# cc2652r_rev_e.net
KiCad netlist of a schematic drawn in EAGLE
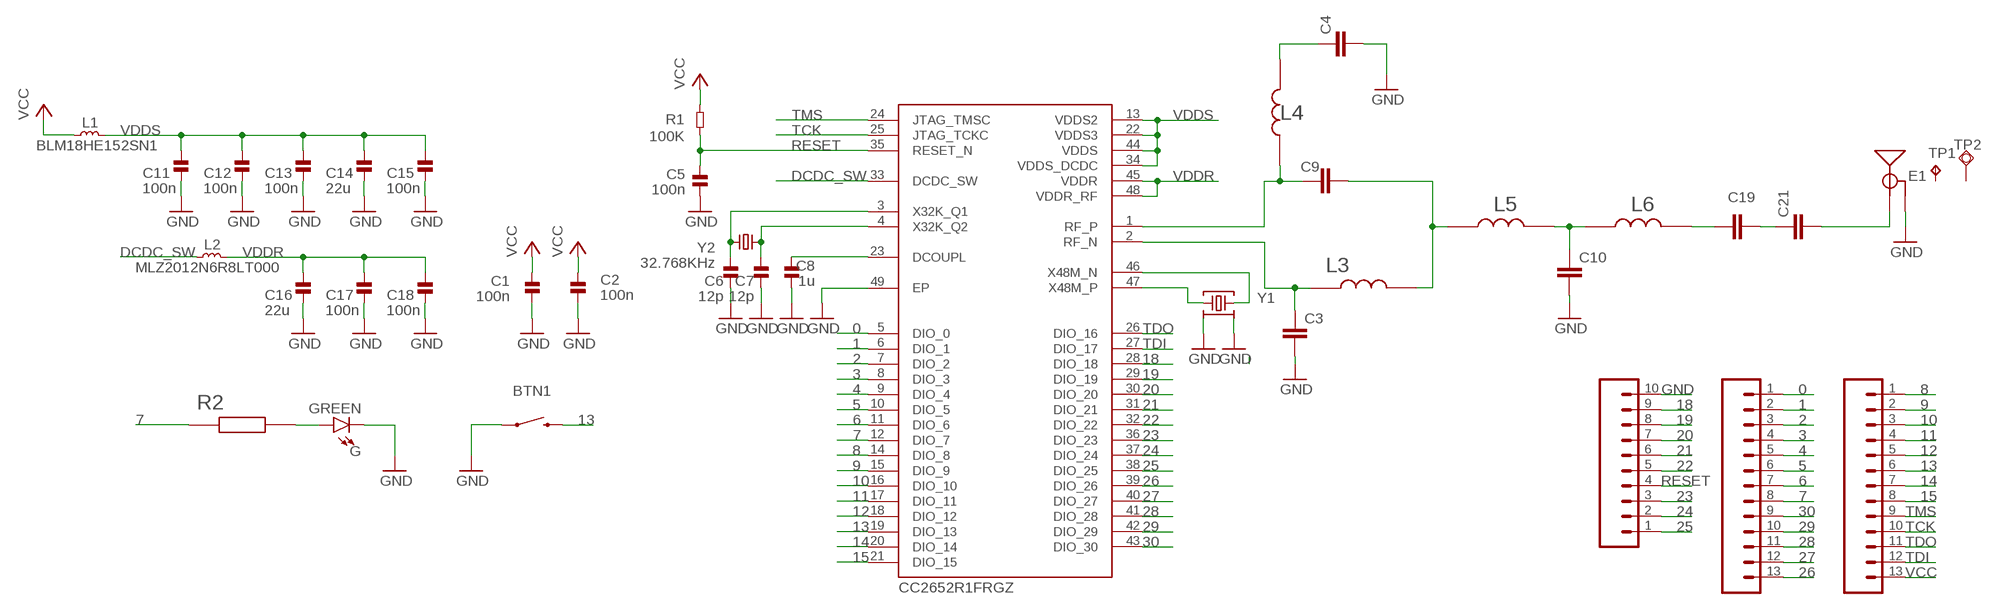
[diagram p0: schematic, sheet 1]

(export (version "E")
  (design (tool "Eeschema 10.0.6"))
  (components
    (comp (ref "BTN1")
      (value "MOMENTARY-SWITCH-SPST-SMD-4.6X2.8MM")
      (footprint "eagle-import:TACTILE_SWITCH_SMD_4.6X2.8MM")
      (libsource (lib "eagle-import") (part "MOMENTARY-SWITCH-SPST-SMD-4.6X2.8MM"))
    )
    (comp (ref "C1")
      (value "100n")
      (footprint "eagle-import:_PKG_C_0402")
      (libsource (lib "eagle-import") (part "CAP-0402"))
    )
    (comp (ref "C2")
      (value "100n")
      (footprint "eagle-import:_PKG_C_0402")
      (libsource (lib "eagle-import") (part "CAP-0402"))
    )
    (comp (ref "C3")
      (value "1pF")
      (footprint "eagle-import:CAPC1005X40N")
      (fields (field (name "MF") "Yageo") (field (name "MP") "RC0402FR-073M6L"))
      (libsource (lib "eagle-import") (part "CAP0402"))
    )
    (comp (ref "C4")
      (value "12pF")
      (footprint "eagle-import:CAPC1005X40N")
      (fields (field (name "MF") "Yageo") (field (name "MP") "RC0402FR-073M6L"))
      (libsource (lib "eagle-import") (part "CAP0402"))
    )
    (comp (ref "C5")
      (value "100n")
      (footprint "eagle-import:_PKG_C_0402")
      (libsource (lib "eagle-import") (part "CAP-0402"))
    )
    (comp (ref "C6")
      (value "12p")
      (footprint "eagle-import:_PKG_C_0402")
      (libsource (lib "eagle-import") (part "CAP-0402"))
    )
    (comp (ref "C7")
      (value "12p")
      (footprint "eagle-import:_PKG_C_0402")
      (libsource (lib "eagle-import") (part "CAP-0402"))
    )
    (comp (ref "C8")
      (value "1u")
      (footprint "eagle-import:_PKG_C_0402")
      (libsource (lib "eagle-import") (part "CAP-0402"))
    )
    (comp (ref "C9")
      (value "1pF")
      (footprint "eagle-import:CAPC1005X40N")
      (fields (field (name "MF") "Yageo") (field (name "MP") "RC0402FR-073M6L"))
      (libsource (lib "eagle-import") (part "CAP0402"))
    )
    (comp (ref "C10")
      (value "1pF")
      (footprint "eagle-import:CAPC1005X40N")
      (fields (field (name "MF") "Yageo") (field (name "MP") "RC0402FR-073M6L"))
      (libsource (lib "eagle-import") (part "CAP0402"))
    )
    (comp (ref "C11")
      (value "100n")
      (footprint "eagle-import:_PKG_C_0402")
      (libsource (lib "eagle-import") (part "CAP-0402"))
    )
    (comp (ref "C12")
      (value "100n")
      (footprint "eagle-import:_PKG_C_0402")
      (libsource (lib "eagle-import") (part "CAP-0402"))
    )
    (comp (ref "C13")
      (value "100n")
      (footprint "eagle-import:_PKG_C_0402")
      (libsource (lib "eagle-import") (part "CAP-0402"))
    )
    (comp (ref "C14")
      (value "22u")
      (footprint "eagle-import:_PKG_C_0805")
      (libsource (lib "eagle-import") (part "CAP-0805"))
    )
    (comp (ref "C15")
      (value "100n")
      (footprint "eagle-import:_PKG_C_0402")
      (libsource (lib "eagle-import") (part "CAP-0402"))
    )
    (comp (ref "C16")
      (value "22u")
      (footprint "eagle-import:_PKG_C_0805")
      (libsource (lib "eagle-import") (part "CAP-0805"))
    )
    (comp (ref "C17")
      (value "100n")
      (footprint "eagle-import:_PKG_C_0402")
      (libsource (lib "eagle-import") (part "CAP-0402"))
    )
    (comp (ref "C18")
      (value "100n")
      (footprint "eagle-import:_PKG_C_0402")
      (libsource (lib "eagle-import") (part "CAP-0402"))
    )
    (comp (ref "C19")
      (value "12pF")
      (footprint "eagle-import:CAPC1005X40N")
      (fields (field (name "MF") "Yageo") (field (name "MP") "RC0402FR-073M6L"))
      (libsource (lib "eagle-import") (part "CAP0402"))
    )
    (comp (ref "C21")
      (value "1.8pF")
      (footprint "eagle-import:CAPC1005X40N")
      (fields (field (name "MF") "Yageo") (field (name "MP") "RC0402FR-073M6L"))
      (libsource (lib "eagle-import") (part "CAP0402"))
    )
    (comp (ref "E1")
      (value "ANTENNA-GROUNDEDTRACE-15.2MM")
      (footprint "eagle-import:TRACE_ANTENNA_2.4GHZ_15.2MM")
      (libsource (lib "eagle-import") (part "ANTENNA-GROUNDEDTRACE-15.2MM"))
    )
    (comp (ref "G")
      (value "GREEN")
      (footprint "eagle-import:LED-0603")
      (libsource (lib "eagle-import") (part "LED-GREEN0603"))
    )
    (comp (ref "IC3")
      (value "CC2652R1FRGZ")
      (footprint "eagle-import:QFN50P700X700X100-49N")
      (fields
        (field (name "MANUFACTURER_PART_NUMBER") "CC2652R1FRGZT")
        (field (name "MOUSER_PART_NUMBER") "595-CC2652R1FRGZT")
      )
      (libsource (lib "eagle-import") (part "WMCU-CC2652R1FRGZ"))
    )
    (comp (ref "J1")
      (value "CONN_051.27MM")
      (footprint "eagle-import:1X05_1.27MM")
      (libsource (lib "eagle-import") (part "CONN_051.27MM"))
    )
    (comp (ref "J2")
      (value "CONN_051.27MM")
      (footprint "eagle-import:1X05_1.27MM")
      (libsource (lib "eagle-import") (part "CONN_051.27MM"))
    )
    (comp (ref "J3")
      (value "CONN_061.27MM")
      (footprint "eagle-import:1X06_1.27MM")
      (libsource (lib "eagle-import") (part "CONN_061.27MM"))
    )
    (comp (ref "L1")
      (value "BLM18HE152SN1")
      (footprint "eagle-import:_PKG_L_0603")
      (libsource (lib "eagle-import") (part "INDUCTOR-0603"))
    )
    (comp (ref "L2")
      (value "MLZ2012N6R8LT000")
      (footprint "eagle-import:_PKG_C_0805")
      (libsource (lib "eagle-import") (part "INDUCTOR-0805"))
    )
    (comp (ref "L3")
      (value "2.4nH")
      (footprint "eagle-import:INDC1005X40N")
      (fields (field (name "MF") "Yageo") (field (name "MP") "RC0402FR-073M6L"))
      (libsource (lib "eagle-import") (part "IND0402IND0402"))
    )
    (comp (ref "L4")
      (value "2.4nH")
      (footprint "eagle-import:INDC1005X40N")
      (fields (field (name "MF") "Yageo") (field (name "MP") "RC0402FR-073M6L"))
      (libsource (lib "eagle-import") (part "IND0402IND0402"))
    )
    (comp (ref "L5")
      (value "2nH")
      (footprint "eagle-import:INDC1005X40N")
      (fields (field (name "MF") "Yageo") (field (name "MP") "RC0402FR-073M6L"))
      (libsource (lib "eagle-import") (part "IND0402IND0402"))
    )
    (comp (ref "L6")
      (value "2nH")
      (footprint "eagle-import:INDC1005X40N")
      (fields (field (name "MF") "Yageo") (field (name "MP") "RC0402FR-073M6L"))
      (libsource (lib "eagle-import") (part "IND0402IND0402"))
    )
    (comp (ref "R1")
      (value "100K")
      (footprint "eagle-import:_PKG_C_0402")
      (libsource (lib "eagle-import") (part "RES-0402"))
    )
    (comp (ref "R2")
      (value "2.2k")
      (footprint "eagle-import:RESC1005X40N")
      (fields (field (name "MF") "Yageo") (field (name "MP") "RC0402FR-073M6L"))
      (libsource (lib "eagle-import") (part "RES0402"))
    )
    (comp (ref "TP1")
      (value "TPTP06SQ")
      (footprint "eagle-import:TP05SQ")
      (libsource (lib "eagle-import") (part "TPTP06SQ"))
    )
    (comp (ref "TP2")
      (value "TPSQTP15SQ")
      (footprint "eagle-import:TP15SQ")
      (libsource (lib "eagle-import") (part "TPSQTP15SQ"))
    )
    (comp (ref "Y1")
      (value "Q22FA12800150")
      (footprint "eagle-import:XTAL-4P-2016")
      (fields (field (name "DIGIKEY_PART") "1253-2042-1-ND") (field (name "MFG_PART") "CX2016DB48000C0FPLC1"))
      (libsource (lib "eagle-import") (part "48.000MHZ_CX2016DB48000C0FPLC1"))
    )
    (comp (ref "Y2")
      (value "32.768KHz")
      (footprint "eagle-import:XTAL-2P-3215")
      (fields (field (name "LCSC_PART") "C32346") (field (name "MFG_PART") "Q13FC1350000400"))
      (libsource (lib "eagle-import") (part "32.768KHZ_Q13FC1350000400"))
    )
  )
  (nets
    (net (code "1") (name "/0") (class "Default")
      (node (ref "IC3") (pin "5") (pinfunction "DIO_0_5") (pintype "bidirectional"))
      (node (ref "J1") (pin "1") (pinfunction "1_1") (pintype "passive"))
    )
    (net (code "2") (name "/1") (class "Default")
      (node (ref "IC3") (pin "6") (pinfunction "DIO_1_6") (pintype "bidirectional"))
      (node (ref "J1") (pin "2") (pinfunction "2_2") (pintype "passive"))
    )
    (net (code "3") (name "/2") (class "Default")
      (node (ref "IC3") (pin "7") (pinfunction "DIO_2_7") (pintype "bidirectional"))
      (node (ref "J1") (pin "3") (pinfunction "3_3") (pintype "passive"))
    )
    (net (code "4") (name "/3") (class "Default")
      (node (ref "IC3") (pin "8") (pinfunction "DIO_3_8") (pintype "bidirectional"))
      (node (ref "J1") (pin "4") (pinfunction "4_4") (pintype "passive"))
    )
    (net (code "5") (name "/4") (class "Default")
      (node (ref "IC3") (pin "9") (pinfunction "DIO_4_9") (pintype "bidirectional"))
      (node (ref "J1") (pin "5") (pinfunction "5_5") (pintype "passive"))
    )
    (net (code "6") (name "/5") (class "Default")
      (node (ref "IC3") (pin "10") (pinfunction "DIO_5_10") (pintype "bidirectional"))
      (node (ref "J1") (pin "6") (pinfunction "6_6") (pintype "passive"))
    )
    (net (code "7") (name "/6") (class "Default")
      (node (ref "IC3") (pin "11") (pinfunction "DIO_6_11") (pintype "bidirectional"))
      (node (ref "J1") (pin "7") (pinfunction "7_7") (pintype "passive"))
    )
    (net (code "8") (name "/7") (class "Default")
      (node (ref "IC3") (pin "12") (pinfunction "DIO_7_12") (pintype "bidirectional"))
      (node (ref "J1") (pin "8") (pinfunction "8_8") (pintype "passive"))
      (node (ref "R2") (pin "1") (pinfunction "1_1") (pintype "passive"))
    )
    (net (code "9") (name "/8") (class "Default")
      (node (ref "IC3") (pin "14") (pinfunction "DIO_8_14") (pintype "bidirectional"))
      (node (ref "J2") (pin "1") (pinfunction "1_1") (pintype "passive"))
    )
    (net (code "10") (name "/9") (class "Default")
      (node (ref "IC3") (pin "15") (pinfunction "DIO_9_15") (pintype "bidirectional"))
      (node (ref "J2") (pin "2") (pinfunction "2_2") (pintype "passive"))
    )
    (net (code "11") (name "/10") (class "Default")
      (node (ref "IC3") (pin "16") (pinfunction "DIO_10_16") (pintype "bidirectional"))
      (node (ref "J2") (pin "3") (pinfunction "3_3") (pintype "passive"))
    )
    (net (code "12") (name "/11") (class "Default")
      (node (ref "IC3") (pin "17") (pinfunction "DIO_11_17") (pintype "bidirectional"))
      (node (ref "J2") (pin "4") (pinfunction "4_4") (pintype "passive"))
    )
    (net (code "13") (name "/12") (class "Default")
      (node (ref "IC3") (pin "18") (pinfunction "DIO_12_18") (pintype "bidirectional"))
      (node (ref "J2") (pin "5") (pinfunction "5_5") (pintype "passive"))
    )
    (net (code "14") (name "/13") (class "Default")
      (node (ref "BTN1") (pin "3") (pinfunction "2_3") (pintype "passive"))
      (node (ref "BTN1") (pin "4") (pinfunction "2_4") (pintype "passive"))
      (node (ref "IC3") (pin "19") (pinfunction "DIO_13_19") (pintype "bidirectional"))
      (node (ref "J2") (pin "6") (pinfunction "6_6") (pintype "passive"))
    )
    (net (code "15") (name "/14") (class "Default")
      (node (ref "IC3") (pin "20") (pinfunction "DIO_14_20") (pintype "bidirectional"))
      (node (ref "J2") (pin "7") (pinfunction "7_7") (pintype "passive"))
    )
    (net (code "16") (name "/15") (class "Default")
      (node (ref "IC3") (pin "21") (pinfunction "DIO_15_21") (pintype "bidirectional"))
      (node (ref "J2") (pin "8") (pinfunction "8_8") (pintype "passive"))
    )
    (net (code "17") (name "/18") (class "Default")
      (node (ref "IC3") (pin "28") (pinfunction "DIO_18_28") (pintype "bidirectional"))
      (node (ref "J3") (pin "9") (pinfunction "9_9") (pintype "passive"))
    )
    (net (code "18") (name "/19") (class "Default")
      (node (ref "IC3") (pin "29") (pinfunction "DIO_19_29") (pintype "bidirectional"))
      (node (ref "J3") (pin "8") (pinfunction "8_8") (pintype "passive"))
    )
    (net (code "19") (name "/20") (class "Default")
      (node (ref "IC3") (pin "30") (pinfunction "DIO_20_30") (pintype "bidirectional"))
      (node (ref "J3") (pin "7") (pinfunction "7_7") (pintype "passive"))
    )
    (net (code "20") (name "/21") (class "Default")
      (node (ref "IC3") (pin "31") (pinfunction "DIO_21_31") (pintype "bidirectional"))
      (node (ref "J3") (pin "6") (pinfunction "6_6") (pintype "passive"))
    )
    (net (code "21") (name "/22") (class "Default")
      (node (ref "IC3") (pin "32") (pinfunction "DIO_22_32") (pintype "bidirectional"))
      (node (ref "J3") (pin "5") (pinfunction "5_5") (pintype "passive"))
    )
    (net (code "22") (name "/23") (class "Default")
      (node (ref "IC3") (pin "36") (pinfunction "DIO_23_36") (pintype "bidirectional"))
      (node (ref "J3") (pin "3") (pinfunction "3_3") (pintype "passive"))
    )
    (net (code "23") (name "/24") (class "Default")
      (node (ref "IC3") (pin "37") (pinfunction "DIO_24_37") (pintype "bidirectional"))
      (node (ref "J3") (pin "2") (pinfunction "2_2") (pintype "passive"))
    )
    (net (code "24") (name "/25") (class "Default")
      (node (ref "IC3") (pin "38") (pinfunction "DIO_25_38") (pintype "bidirectional"))
      (node (ref "J3") (pin "1") (pinfunction "1_1") (pintype "passive"))
    )
    (net (code "25") (name "/26") (class "Default")
      (node (ref "IC3") (pin "39") (pinfunction "DIO_26_39") (pintype "bidirectional"))
      (node (ref "J1") (pin "13") (pinfunction "13_13") (pintype "passive"))
    )
    (net (code "26") (name "/27") (class "Default")
      (node (ref "IC3") (pin "40") (pinfunction "DIO_27_40") (pintype "bidirectional"))
      (node (ref "J1") (pin "12") (pinfunction "12_12") (pintype "passive"))
    )
    (net (code "27") (name "/28") (class "Default")
      (node (ref "IC3") (pin "41") (pinfunction "DIO_28_41") (pintype "bidirectional"))
      (node (ref "J1") (pin "11") (pinfunction "11_11") (pintype "passive"))
    )
    (net (code "28") (name "/29") (class "Default")
      (node (ref "IC3") (pin "42") (pinfunction "DIO_29_42") (pintype "bidirectional"))
      (node (ref "J1") (pin "10") (pinfunction "10_10") (pintype "passive"))
    )
    (net (code "29") (name "/30") (class "Default")
      (node (ref "IC3") (pin "43") (pinfunction "DIO_30_43") (pintype "bidirectional"))
      (node (ref "J1") (pin "9") (pinfunction "9_9") (pintype "passive"))
    )
    (net (code "30") (name "/DCDC_SW") (class "Default")
      (node (ref "IC3") (pin "33") (pinfunction "DCDC_SW_33") (pintype "bidirectional"))
      (node (ref "L2") (pin "1") (pinfunction "1_1") (pintype "passive"))
    )
    (net (code "31") (name "/RESET") (class "Default")
      (node (ref "C5") (pin "2") (pinfunction "2_2") (pintype "passive"))
      (node (ref "IC3") (pin "35") (pinfunction "RESET_N_35") (pintype "bidirectional"))
      (node (ref "J3") (pin "4") (pinfunction "4_4") (pintype "passive"))
      (node (ref "R1") (pin "1") (pinfunction "1_1") (pintype "passive"))
    )
    (net (code "32") (name "/TCK") (class "Default")
      (node (ref "IC3") (pin "25") (pinfunction "JTAG_TCKC_25") (pintype "bidirectional"))
      (node (ref "J2") (pin "10") (pinfunction "10_10") (pintype "passive"))
    )
    (net (code "33") (name "/TDI") (class "Default")
      (node (ref "IC3") (pin "27") (pinfunction "DIO_17_27") (pintype "bidirectional"))
      (node (ref "J2") (pin "12") (pinfunction "12_12") (pintype "passive"))
    )
    (net (code "34") (name "/TDO") (class "Default")
      (node (ref "IC3") (pin "26") (pinfunction "DIO_16_26") (pintype "bidirectional"))
      (node (ref "J2") (pin "11") (pinfunction "11_11") (pintype "passive"))
    )
    (net (code "35") (name "/TMS") (class "Default")
      (node (ref "IC3") (pin "24") (pinfunction "JTAG_TMSC_24") (pintype "bidirectional"))
      (node (ref "J2") (pin "9") (pinfunction "9_9") (pintype "passive"))
    )
    (net (code "36") (name "/VDDR") (class "Default")
      (node (ref "C16") (pin "1") (pinfunction "1_1") (pintype "passive"))
      (node (ref "C17") (pin "1") (pinfunction "1_1") (pintype "passive"))
      (node (ref "C18") (pin "1") (pinfunction "1_1") (pintype "passive"))
      (node (ref "IC3") (pin "45") (pinfunction "VDDR_45") (pintype "bidirectional"))
      (node (ref "IC3") (pin "48") (pinfunction "VDDR_RF_48") (pintype "bidirectional"))
      (node (ref "L2") (pin "2") (pinfunction "2_2") (pintype "passive"))
    )
    (net (code "37") (name "/VDDS") (class "Default")
      (node (ref "C11") (pin "1") (pinfunction "1_1") (pintype "passive"))
      (node (ref "C12") (pin "1") (pinfunction "1_1") (pintype "passive"))
      (node (ref "C13") (pin "1") (pinfunction "1_1") (pintype "passive"))
      (node (ref "C14") (pin "1") (pinfunction "1_1") (pintype "passive"))
      (node (ref "C15") (pin "1") (pinfunction "1_1") (pintype "passive"))
      (node (ref "IC3") (pin "13") (pinfunction "VDDS2_13") (pintype "bidirectional"))
      (node (ref "IC3") (pin "22") (pinfunction "VDDS3_22") (pintype "bidirectional"))
      (node (ref "IC3") (pin "34") (pinfunction "VDDS_DCDC_34") (pintype "bidirectional"))
      (node (ref "IC3") (pin "44") (pinfunction "VDDS_44") (pintype "bidirectional"))
      (node (ref "L1") (pin "2") (pinfunction "2_2") (pintype "passive"))
    )
    (net (code "38") (name "GND") (class "Default")
      (node (ref "BTN1") (pin "1") (pinfunction "1_1") (pintype "passive"))
      (node (ref "BTN1") (pin "2") (pinfunction "1_2") (pintype "passive"))
      (node (ref "C1") (pin "1") (pinfunction "1_1") (pintype "passive"))
      (node (ref "C10") (pin "2") (pinfunction "2_2") (pintype "passive"))
      (node (ref "C11") (pin "2") (pinfunction "2_2") (pintype "passive"))
      (node (ref "C12") (pin "2") (pinfunction "2_2") (pintype "passive"))
      (node (ref "C13") (pin "2") (pinfunction "2_2") (pintype "passive"))
      (node (ref "C14") (pin "2") (pinfunction "2_2") (pintype "passive"))
      (node (ref "C15") (pin "2") (pinfunction "2_2") (pintype "passive"))
      (node (ref "C16") (pin "2") (pinfunction "2_2") (pintype "passive"))
      (node (ref "C17") (pin "2") (pinfunction "2_2") (pintype "passive"))
      (node (ref "C18") (pin "2") (pinfunction "2_2") (pintype "passive"))
      (node (ref "C2") (pin "1") (pinfunction "1_1") (pintype "passive"))
      (node (ref "C3") (pin "2") (pinfunction "2_2") (pintype "passive"))
      (node (ref "C4") (pin "2") (pinfunction "2_2") (pintype "passive"))
      (node (ref "C5") (pin "1") (pinfunction "1_1") (pintype "passive"))
      (node (ref "C6") (pin "1") (pinfunction "1_1") (pintype "passive"))
      (node (ref "C7") (pin "1") (pinfunction "1_1") (pintype "passive"))
      (node (ref "C8") (pin "1") (pinfunction "1_1") (pintype "passive"))
      (node (ref "E1") (pin "GND") (pinfunction "GND_GND") (pintype "bidirectional"))
      (node (ref "G") (pin "C") (pinfunction "C_C") (pintype "passive"))
      (node (ref "IC3") (pin "49") (pinfunction "EP_49") (pintype "bidirectional"))
      (node (ref "J3") (pin "10") (pinfunction "10_10") (pintype "passive"))
      (node (ref "Y1") (pin "2") (pinfunction "2_2") (pintype "bidirectional"))
      (node (ref "Y1") (pin "4") (pinfunction "4_4") (pintype "bidirectional"))
    )
    (net (code "39") (name "Net-(C4-Pad1)") (class "Default")
      (node (ref "C4") (pin "1") (pinfunction "1_1") (pintype "passive"))
      (node (ref "L4") (pin "2") (pinfunction "2_2") (pintype "passive"))
    )
    (net (code "40") (name "Net-(C9-Pad2)") (class "Default")
      (node (ref "C9") (pin "2") (pinfunction "2_2") (pintype "passive"))
      (node (ref "L3") (pin "2") (pinfunction "2_2") (pintype "passive"))
      (node (ref "L5") (pin "1") (pinfunction "1_1") (pintype "passive"))
    )
    (net (code "41") (name "Net-(C10-Pad1)") (class "Default")
      (node (ref "C10") (pin "1") (pinfunction "1_1") (pintype "passive"))
      (node (ref "L5") (pin "2") (pinfunction "2_2") (pintype "passive"))
      (node (ref "L6") (pin "1") (pinfunction "1_1") (pintype "passive"))
    )
    (net (code "42") (name "Net-(C19-Pad1)") (class "Default")
      (node (ref "C19") (pin "1") (pinfunction "1_1") (pintype "passive"))
      (node (ref "L6") (pin "2") (pinfunction "2_2") (pintype "passive"))
    )
    (net (code "43") (name "Net-(C19-Pad2)") (class "Default")
      (node (ref "C19") (pin "2") (pinfunction "2_2") (pintype "passive"))
      (node (ref "C21") (pin "1") (pinfunction "1_1") (pintype "passive"))
    )
    (net (code "44") (name "Net-(E1-SIGNAL)") (class "Default")
      (node (ref "C21") (pin "2") (pinfunction "2_2") (pintype "passive"))
      (node (ref "E1") (pin "ANT") (pinfunction "SIGNAL_ANT") (pintype "bidirectional"))
    )
    (net (code "45") (name "Net-(G-PadA)") (class "Default")
      (node (ref "G") (pin "A") (pinfunction "A_A") (pintype "passive"))
      (node (ref "R2") (pin "2") (pinfunction "2_2") (pintype "passive"))
    )
    (net (code "46") (name "Net-(IC3-DCOUPL)") (class "Default")
      (node (ref "C8") (pin "2") (pinfunction "2_2") (pintype "passive"))
      (node (ref "IC3") (pin "23") (pinfunction "DCOUPL_23") (pintype "bidirectional"))
    )
    (net (code "47") (name "Net-(IC3-RF_N)") (class "Default")
      (node (ref "C3") (pin "1") (pinfunction "1_1") (pintype "passive"))
      (node (ref "IC3") (pin "2") (pinfunction "RF_N_2") (pintype "bidirectional"))
      (node (ref "L3") (pin "1") (pinfunction "1_1") (pintype "passive"))
    )
    (net (code "48") (name "Net-(IC3-RF_P)") (class "Default")
      (node (ref "C9") (pin "1") (pinfunction "1_1") (pintype "passive"))
      (node (ref "IC3") (pin "1") (pinfunction "RF_P_1") (pintype "bidirectional"))
      (node (ref "L4") (pin "1") (pinfunction "1_1") (pintype "passive"))
    )
    (net (code "49") (name "Net-(IC3-X32K_Q1)") (class "Default")
      (node (ref "C6") (pin "2") (pinfunction "2_2") (pintype "passive"))
      (node (ref "IC3") (pin "3") (pinfunction "X32K_Q1_3") (pintype "bidirectional"))
      (node (ref "Y2") (pin "1") (pinfunction "1_1") (pintype "passive"))
    )
    (net (code "50") (name "Net-(IC3-X32K_Q2)") (class "Default")
      (node (ref "C7") (pin "2") (pinfunction "2_2") (pintype "passive"))
      (node (ref "IC3") (pin "4") (pinfunction "X32K_Q2_4") (pintype "bidirectional"))
      (node (ref "Y2") (pin "2") (pinfunction "2_2") (pintype "passive"))
    )
    (net (code "51") (name "Net-(IC3-X48M_N)") (class "Default")
      (node (ref "IC3") (pin "46") (pinfunction "X48M_N_46") (pintype "bidirectional"))
      (node (ref "Y1") (pin "3") (pinfunction "3_3") (pintype "passive"))
    )
    (net (code "52") (name "Net-(IC3-X48M_P)") (class "Default")
      (node (ref "IC3") (pin "47") (pinfunction "X48M_P_47") (pintype "bidirectional"))
      (node (ref "Y1") (pin "1") (pinfunction "1_1") (pintype "passive"))
    )
    (net (code "53") (name "VCC") (class "Default")
      (node (ref "C1") (pin "2") (pinfunction "2_2") (pintype "passive"))
      (node (ref "C2") (pin "2") (pinfunction "2_2") (pintype "passive"))
      (node (ref "J2") (pin "13") (pinfunction "13_13") (pintype "passive"))
      (node (ref "L1") (pin "1") (pinfunction "1_1") (pintype "passive"))
      (node (ref "R1") (pin "2") (pinfunction "2_2") (pintype "passive"))
    )
    (net (code "54") (name "unconnected-(TP1-PadTP)") (class "Default")
      (node (ref "TP1") (pin "TP") (pinfunction "TP_TP") (pintype "input"))
    )
    (net (code "55") (name "unconnected-(TP2-PadTP)") (class "Default")
      (node (ref "TP2") (pin "TP") (pinfunction "TP_TP") (pintype "input"))
    )
  )
)
